# M452x.net
KiCad netlist of a schematic drawn in EAGLE
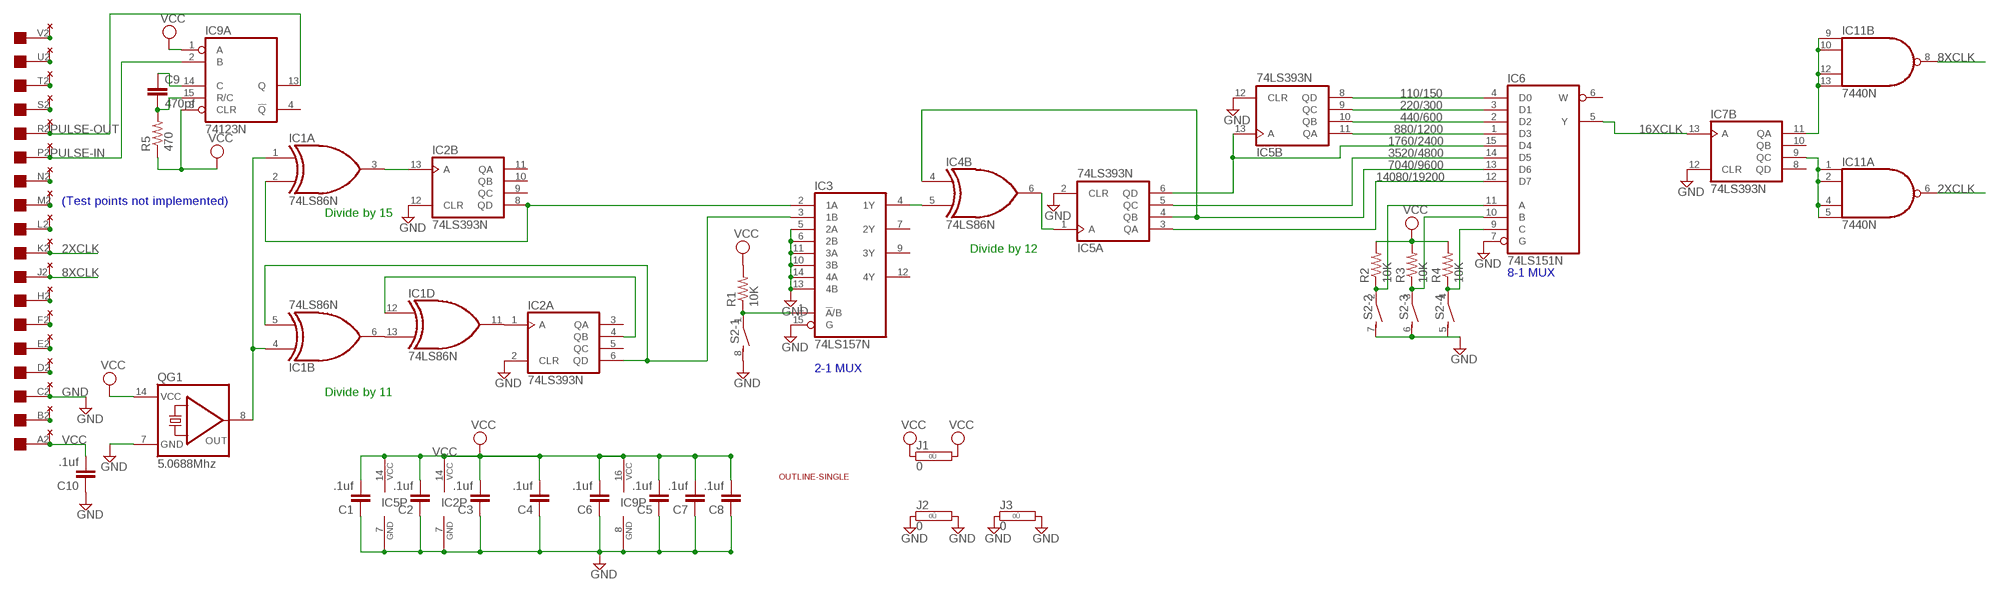
[diagram p0: schematic, sheet 1]

(export (version "E")
  (design (tool "Eeschema 10.0.6"))
  (components
    (comp (ref "C1")
      (value ".1uf")
      (footprint "eagle-import:C050-025X075")
      (libsource (lib "eagle-import") (part "C-EU050-025X075"))
    )
    (comp (ref "C2")
      (value ".1uf")
      (footprint "eagle-import:C050-025X075")
      (libsource (lib "eagle-import") (part "C-EU050-025X075"))
    )
    (comp (ref "C3")
      (value ".1uf")
      (footprint "eagle-import:C050-025X075")
      (libsource (lib "eagle-import") (part "C-EU050-025X075"))
    )
    (comp (ref "C4")
      (value ".1uf")
      (footprint "eagle-import:C050-025X075")
      (libsource (lib "eagle-import") (part "C-EU050-025X075"))
    )
    (comp (ref "C5")
      (value ".1uf")
      (footprint "eagle-import:C050-025X075")
      (libsource (lib "eagle-import") (part "C-EU050-025X075"))
    )
    (comp (ref "C6")
      (value ".1uf")
      (footprint "eagle-import:C050-025X075")
      (libsource (lib "eagle-import") (part "C-EU050-025X075"))
    )
    (comp (ref "C7")
      (value ".1uf")
      (footprint "eagle-import:C050-025X075")
      (libsource (lib "eagle-import") (part "C-EU050-025X075"))
    )
    (comp (ref "C8")
      (value ".1uf")
      (footprint "eagle-import:C050-025X075")
      (libsource (lib "eagle-import") (part "C-EU050-025X075"))
    )
    (comp (ref "C9")
      (value "470pf")
      (footprint "eagle-import:C050-025X075")
      (libsource (lib "eagle-import") (part "C-EU050-025X075"))
    )
    (comp (ref "C10")
      (value ".1uf")
      (footprint "eagle-import:C050-025X075")
      (libsource (lib "eagle-import") (part "C-EU050-025X075"))
    )
    (comp (ref "IC1")
      (value "74LS86N")
      (footprint "eagle-import:DIL14")
      (libsource (lib "eagle-import") (part "7486NLS"))
    )
    (comp (ref "IC2")
      (value "74LS393N")
      (footprint "eagle-import:DIL14")
      (libsource (lib "eagle-import") (part "74393NLS"))
    )
    (comp (ref "IC3")
      (value "74LS157N")
      (footprint "eagle-import:DIL16")
      (libsource (lib "eagle-import") (part "74157NLS"))
    )
    (comp (ref "IC4")
      (value "74LS86N")
      (footprint "eagle-import:DIL14")
      (libsource (lib "eagle-import") (part "7486NLS"))
    )
    (comp (ref "IC5")
      (value "74LS393N")
      (footprint "eagle-import:DIL14")
      (libsource (lib "eagle-import") (part "74393NLS"))
    )
    (comp (ref "IC6")
      (value "74LS151N")
      (footprint "eagle-import:DIL16")
      (libsource (lib "eagle-import") (part "74151N"))
    )
    (comp (ref "IC7")
      (value "74LS393N")
      (footprint "eagle-import:DIL14")
      (libsource (lib "eagle-import") (part "74393NLS"))
    )
    (comp (ref "IC9")
      (value "74123N")
      (footprint "eagle-import:DIL16")
      (libsource (lib "eagle-import") (part "74123N"))
    )
    (comp (ref "IC11")
      (value "7440N")
      (footprint "eagle-import:DIL14")
      (libsource (lib "eagle-import") (part "7420NS"))
    )
    (comp (ref "J1")
      (value "0")
      (footprint "eagle-import:0R_10")
      (libsource (lib "eagle-import") (part "0R"))
    )
    (comp (ref "J2")
      (value "0")
      (footprint "eagle-import:0R_10")
      (libsource (lib "eagle-import") (part "0R"))
    )
    (comp (ref "J3")
      (value "0")
      (footprint "eagle-import:0R_10")
      (libsource (lib "eagle-import") (part "0R"))
    )
    (comp (ref "QG1")
      (value "5.0688Mhz")
      (footprint "eagle-import:DIL14S")
      (libsource (lib "eagle-import") (part "QG5860"))
    )
    (comp (ref "R1")
      (value "10K")
      (footprint "eagle-import:0204_7")
      (libsource (lib "eagle-import") (part "R-US_0204/7"))
    )
    (comp (ref "R2")
      (value "10K")
      (footprint "eagle-import:0204_7")
      (libsource (lib "eagle-import") (part "R-US_0204/7"))
    )
    (comp (ref "R3")
      (value "10K")
      (footprint "eagle-import:0204_7")
      (libsource (lib "eagle-import") (part "R-US_0204/7"))
    )
    (comp (ref "R4")
      (value "10K")
      (footprint "eagle-import:0204_7")
      (libsource (lib "eagle-import") (part "R-US_0204/7"))
    )
    (comp (ref "R5")
      (value "470")
      (footprint "eagle-import:0204_7")
      (libsource (lib "eagle-import") (part "R-US_0204/7"))
    )
    (comp (ref "S2")
      (value "DIP04S")
      (footprint "eagle-import:DIP04S")
      (libsource (lib "eagle-import") (part "DIP04S"))
    )
    (comp (ref "U$2")
      (value "THRU-HOLE1")
      (footprint "eagle-import:THRU-HOLE1")
      (libsource (lib "eagle-import") (part "THRU-HOLE1"))
    )
    (comp (ref "U$3")
      (value "OUTLINE-SINGLE")
      (footprint "eagle-import:SINGLE")
      (libsource (lib "eagle-import") (part "OUTLINE-SINGLE"))
    )
    (comp (ref "U$4")
      (value "EDGE-1")
      (footprint "eagle-import:EDGE-CON1")
      (libsource (lib "eagle-import") (part "EDGE-1"))
    )
  )
  (nets
    (net (code "1") (name "/2XCLK") (class "Default")
      (node (ref "IC11") (pin "6") (pinfunction "O_6") (pintype "output"))
      (node (ref "U$2") (pin "K2") (pinfunction "P$1_K2") (pintype "passive"))
      (node (ref "U$4") (pin "K2") (pinfunction "1_K2") (pintype "bidirectional"))
    )
    (net (code "2") (name "/8XCLK") (class "Default")
      (node (ref "IC11") (pin "8") (pinfunction "O_8") (pintype "output"))
      (node (ref "U$2") (pin "J2") (pinfunction "P$1_J2") (pintype "passive"))
      (node (ref "U$4") (pin "J2") (pinfunction "1_J2") (pintype "bidirectional"))
    )
    (net (code "3") (name "/16XCLK") (class "Default")
      (node (ref "IC6") (pin "5") (pinfunction "Y_5") (pintype "output"))
      (node (ref "IC7") (pin "13") (pinfunction "A_13") (pintype "input"))
    )
    (net (code "4") (name "/110{slash}150") (class "Default")
      (node (ref "IC5") (pin "8") (pinfunction "QD_8") (pintype "output"))
      (node (ref "IC6") (pin "4") (pinfunction "D0_4") (pintype "input"))
    )
    (net (code "5") (name "/220{slash}300") (class "Default")
      (node (ref "IC5") (pin "9") (pinfunction "QC_9") (pintype "output"))
      (node (ref "IC6") (pin "3") (pinfunction "D1_3") (pintype "input"))
    )
    (net (code "6") (name "/440{slash}600") (class "Default")
      (node (ref "IC5") (pin "10") (pinfunction "QB_10") (pintype "output"))
      (node (ref "IC6") (pin "2") (pinfunction "D2_2") (pintype "input"))
    )
    (net (code "7") (name "/880{slash}1200") (class "Default")
      (node (ref "IC5") (pin "11") (pinfunction "QA_11") (pintype "output"))
      (node (ref "IC6") (pin "1") (pinfunction "D3_1") (pintype "input"))
    )
    (net (code "8") (name "/1760{slash}2400") (class "Default")
      (node (ref "IC5") (pin "13") (pinfunction "A_13") (pintype "input"))
      (node (ref "IC5") (pin "6") (pinfunction "QD_6") (pintype "output"))
      (node (ref "IC6") (pin "15") (pinfunction "D4_15") (pintype "input"))
    )
    (net (code "9") (name "/3520{slash}4800") (class "Default")
      (node (ref "IC5") (pin "5") (pinfunction "QC_5") (pintype "output"))
      (node (ref "IC6") (pin "14") (pinfunction "D5_14") (pintype "input"))
    )
    (net (code "10") (name "/7040{slash}9600") (class "Default")
      (node (ref "IC4") (pin "4") (pinfunction "I0_4") (pintype "input"))
      (node (ref "IC5") (pin "4") (pinfunction "QB_4") (pintype "output"))
      (node (ref "IC6") (pin "13") (pinfunction "D6_13") (pintype "input"))
    )
    (net (code "11") (name "/14080{slash}19200") (class "Default")
      (node (ref "IC5") (pin "3") (pinfunction "QA_3") (pintype "output"))
      (node (ref "IC6") (pin "12") (pinfunction "D7_12") (pintype "input"))
    )
    (net (code "12") (name "/PULSE-IN") (class "Default")
      (node (ref "IC9") (pin "2") (pinfunction "B_2") (pintype "input"))
      (node (ref "U$2") (pin "P2") (pinfunction "P$1_P2") (pintype "passive"))
      (node (ref "U$4") (pin "P2") (pinfunction "1_P2") (pintype "bidirectional"))
    )
    (net (code "13") (name "/PULSE-OUT") (class "Default")
      (node (ref "IC9") (pin "13") (pinfunction "Q_13") (pintype "output"))
      (node (ref "U$2") (pin "R2") (pinfunction "P$1_R2") (pintype "passive"))
      (node (ref "U$4") (pin "R2") (pinfunction "1_R2") (pintype "bidirectional"))
    )
    (net (code "14") (name "GND") (class "Default")
      (node (ref "C1") (pin "1") (pinfunction "1_1") (pintype "passive"))
      (node (ref "C10") (pin "1") (pinfunction "1_1") (pintype "passive"))
      (node (ref "C2") (pin "1") (pinfunction "1_1") (pintype "passive"))
      (node (ref "C3") (pin "1") (pinfunction "1_1") (pintype "passive"))
      (node (ref "C4") (pin "1") (pinfunction "1_1") (pintype "passive"))
      (node (ref "C5") (pin "1") (pinfunction "1_1") (pintype "passive"))
      (node (ref "C6") (pin "1") (pinfunction "1_1") (pintype "passive"))
      (node (ref "C7") (pin "1") (pinfunction "1_1") (pintype "passive"))
      (node (ref "C8") (pin "1") (pinfunction "1_1") (pintype "passive"))
      (node (ref "IC2") (pin "12") (pinfunction "CLR_12") (pintype "input"))
      (node (ref "IC2") (pin "2") (pinfunction "CLR_2") (pintype "input"))
      (node (ref "IC2") (pin "7") (pinfunction "GND_7") (pintype "power_in"))
      (node (ref "IC3") (pin "10") (pinfunction "3B_10") (pintype "input"))
      (node (ref "IC3") (pin "11") (pinfunction "3A_11") (pintype "input"))
      (node (ref "IC3") (pin "13") (pinfunction "4B_13") (pintype "input"))
      (node (ref "IC3") (pin "14") (pinfunction "4A_14") (pintype "input"))
      (node (ref "IC3") (pin "15") (pinfunction "G_15") (pintype "input"))
      (node (ref "IC3") (pin "5") (pinfunction "2A_5") (pintype "input"))
      (node (ref "IC3") (pin "6") (pinfunction "2B_6") (pintype "input"))
      (node (ref "IC5") (pin "12") (pinfunction "CLR_12") (pintype "input"))
      (node (ref "IC5") (pin "2") (pinfunction "CLR_2") (pintype "input"))
      (node (ref "IC5") (pin "7") (pinfunction "GND_7") (pintype "power_in"))
      (node (ref "IC6") (pin "7") (pinfunction "G_7") (pintype "input"))
      (node (ref "IC7") (pin "12") (pinfunction "CLR_12") (pintype "input"))
      (node (ref "IC9") (pin "8") (pinfunction "GND_8") (pintype "power_in"))
      (node (ref "J2") (pin "1") (pinfunction "1_1") (pintype "passive"))
      (node (ref "J2") (pin "2") (pinfunction "2_2") (pintype "passive"))
      (node (ref "J3") (pin "1") (pinfunction "1_1") (pintype "passive"))
      (node (ref "J3") (pin "2") (pinfunction "2_2") (pintype "passive"))
      (node (ref "QG1") (pin "7") (pinfunction "GND_7") (pintype "power_in"))
      (node (ref "S2") (pin "5") (pinfunction "2_5") (pintype "passive"))
      (node (ref "S2") (pin "6") (pinfunction "2_6") (pintype "passive"))
      (node (ref "S2") (pin "7") (pinfunction "2_7") (pintype "passive"))
      (node (ref "S2") (pin "8") (pinfunction "2_8") (pintype "passive"))
      (node (ref "U$2") (pin "C2") (pinfunction "P$1_C2") (pintype "passive"))
      (node (ref "U$4") (pin "C2") (pinfunction "1_C2") (pintype "bidirectional"))
    )
    (net (code "15") (name "Net-(IC1A-I0)") (class "Default")
      (node (ref "IC1") (pin "1") (pinfunction "I0_1") (pintype "input"))
      (node (ref "IC1") (pin "4") (pinfunction "I0_4") (pintype "input"))
      (node (ref "QG1") (pin "8") (pinfunction "OUT_8") (pintype "output"))
    )
    (net (code "16") (name "Net-(IC1A-I1)") (class "Default")
      (node (ref "IC1") (pin "2") (pinfunction "I1_2") (pintype "input"))
      (node (ref "IC2") (pin "8") (pinfunction "QD_8") (pintype "output"))
      (node (ref "IC3") (pin "2") (pinfunction "1A_2") (pintype "input"))
    )
    (net (code "17") (name "Net-(IC1A-O)") (class "Default")
      (node (ref "IC1") (pin "3") (pinfunction "O_3") (pintype "output"))
      (node (ref "IC2") (pin "13") (pinfunction "A_13") (pintype "input"))
    )
    (net (code "18") (name "Net-(IC1B-I1)") (class "Default")
      (node (ref "IC1") (pin "5") (pinfunction "I1_5") (pintype "input"))
      (node (ref "IC2") (pin "6") (pinfunction "QD_6") (pintype "output"))
      (node (ref "IC3") (pin "3") (pinfunction "1B_3") (pintype "input"))
    )
    (net (code "19") (name "Net-(IC1B-O)") (class "Default")
      (node (ref "IC1") (pin "13") (pinfunction "I1_13") (pintype "input"))
      (node (ref "IC1") (pin "6") (pinfunction "O_6") (pintype "output"))
    )
    (net (code "20") (name "Net-(IC1D-I0)") (class "Default")
      (node (ref "IC1") (pin "12") (pinfunction "I0_12") (pintype "input"))
      (node (ref "IC2") (pin "4") (pinfunction "QB_4") (pintype "output"))
    )
    (net (code "21") (name "Net-(IC1D-O)") (class "Default")
      (node (ref "IC1") (pin "11") (pinfunction "O_11") (pintype "output"))
      (node (ref "IC2") (pin "1") (pinfunction "A_1") (pintype "input"))
    )
    (net (code "22") (name "Net-(IC3A-1Y)") (class "Default")
      (node (ref "IC3") (pin "4") (pinfunction "1Y_4") (pintype "output"))
      (node (ref "IC4") (pin "5") (pinfunction "I1_5") (pintype "input"))
    )
    (net (code "23") (name "Net-(IC3A-~{A}{slash}B)") (class "Default")
      (node (ref "IC3") (pin "1") (pinfunction "~{A}/B_1") (pintype "input"))
      (node (ref "R1") (pin "1") (pinfunction "1_1") (pintype "passive"))
      (node (ref "S2") (pin "1") (pinfunction "1_1") (pintype "passive"))
    )
    (net (code "24") (name "Net-(IC4B-O)") (class "Default")
      (node (ref "IC4") (pin "6") (pinfunction "O_6") (pintype "output"))
      (node (ref "IC5") (pin "1") (pinfunction "A_1") (pintype "input"))
    )
    (net (code "25") (name "Net-(IC6A-A)") (class "Default")
      (node (ref "IC6") (pin "11") (pinfunction "A_11") (pintype "input"))
      (node (ref "R2") (pin "1") (pinfunction "1_1") (pintype "passive"))
      (node (ref "S2") (pin "2") (pinfunction "1_2") (pintype "passive"))
    )
    (net (code "26") (name "Net-(IC6A-B)") (class "Default")
      (node (ref "IC6") (pin "10") (pinfunction "B_10") (pintype "input"))
      (node (ref "R3") (pin "1") (pinfunction "1_1") (pintype "passive"))
      (node (ref "S2") (pin "3") (pinfunction "1_3") (pintype "passive"))
    )
    (net (code "27") (name "Net-(IC6A-C)") (class "Default")
      (node (ref "IC6") (pin "9") (pinfunction "C_9") (pintype "input"))
      (node (ref "R4") (pin "1") (pinfunction "1_1") (pintype "passive"))
      (node (ref "S2") (pin "4") (pinfunction "1_4") (pintype "passive"))
    )
    (net (code "28") (name "Net-(IC9A-C)") (class "Default")
      (node (ref "C9") (pin "1") (pinfunction "1_1") (pintype "passive"))
      (node (ref "IC9") (pin "14") (pinfunction "C_14") (pintype "input"))
    )
    (net (code "29") (name "Net-(IC9A-R{slash}C)") (class "Default")
      (node (ref "C9") (pin "2") (pinfunction "2_2") (pintype "passive"))
      (node (ref "IC9") (pin "15") (pinfunction "R/C_15") (pintype "input"))
      (node (ref "R5") (pin "2") (pinfunction "2_2") (pintype "passive"))
    )
    (net (code "30") (name "Net-(IC11A-I0)") (class "Default")
      (node (ref "IC11") (pin "1") (pinfunction "I0_1") (pintype "input"))
      (node (ref "IC11") (pin "2") (pinfunction "I1_2") (pintype "input"))
      (node (ref "IC11") (pin "4") (pinfunction "I2_4") (pintype "input"))
      (node (ref "IC11") (pin "5") (pinfunction "I3_5") (pintype "input"))
      (node (ref "IC7") (pin "9") (pinfunction "QC_9") (pintype "output"))
    )
    (net (code "31") (name "Net-(IC11B-I0)") (class "Default")
      (node (ref "IC11") (pin "10") (pinfunction "I1_10") (pintype "input"))
      (node (ref "IC11") (pin "12") (pinfunction "I2_12") (pintype "input"))
      (node (ref "IC11") (pin "13") (pinfunction "I3_13") (pintype "input"))
      (node (ref "IC11") (pin "9") (pinfunction "I0_9") (pintype "input"))
      (node (ref "IC7") (pin "11") (pinfunction "QA_11") (pintype "output"))
    )
    (net (code "32") (name "Net-(U$2B-P$1)") (class "Default")
      (node (ref "U$2") (pin "B2") (pinfunction "P$1_B2") (pintype "passive"))
      (node (ref "U$4") (pin "B2") (pinfunction "1_B2") (pintype "bidirectional"))
    )
    (net (code "33") (name "Net-(U$2D-P$1)") (class "Default")
      (node (ref "U$2") (pin "D2") (pinfunction "P$1_D2") (pintype "passive"))
      (node (ref "U$4") (pin "D2") (pinfunction "1_D2") (pintype "bidirectional"))
    )
    (net (code "34") (name "Net-(U$2E-P$1)") (class "Default")
      (node (ref "U$2") (pin "E2") (pinfunction "P$1_E2") (pintype "passive"))
      (node (ref "U$4") (pin "E2") (pinfunction "1_E2") (pintype "bidirectional"))
    )
    (net (code "35") (name "Net-(U$2F-P$1)") (class "Default")
      (node (ref "U$2") (pin "F2") (pinfunction "P$1_F2") (pintype "passive"))
      (node (ref "U$4") (pin "F2") (pinfunction "1_F2") (pintype "bidirectional"))
    )
    (net (code "36") (name "Net-(U$2G-P$1)") (class "Default")
      (node (ref "U$2") (pin "H2") (pinfunction "P$1_H2") (pintype "passive"))
      (node (ref "U$4") (pin "H2") (pinfunction "1_H2") (pintype "bidirectional"))
    )
    (net (code "37") (name "Net-(U$2J-P$1)") (class "Default")
      (node (ref "U$2") (pin "L2") (pinfunction "P$1_L2") (pintype "passive"))
      (node (ref "U$4") (pin "L2") (pinfunction "1_L2") (pintype "bidirectional"))
    )
    (net (code "38") (name "Net-(U$2K-P$1)") (class "Default")
      (node (ref "U$2") (pin "M2") (pinfunction "P$1_M2") (pintype "passive"))
      (node (ref "U$4") (pin "M2") (pinfunction "1_M2") (pintype "bidirectional"))
    )
    (net (code "39") (name "Net-(U$2L-P$1)") (class "Default")
      (node (ref "U$2") (pin "N2") (pinfunction "P$1_N2") (pintype "passive"))
      (node (ref "U$4") (pin "N2") (pinfunction "1_N2") (pintype "bidirectional"))
    )
    (net (code "40") (name "Net-(U$2O-P$1)") (class "Default")
      (node (ref "U$2") (pin "S2") (pinfunction "P$1_S2") (pintype "passive"))
      (node (ref "U$4") (pin "S2") (pinfunction "1_S2") (pintype "bidirectional"))
    )
    (net (code "41") (name "Net-(U$2P-P$1)") (class "Default")
      (node (ref "U$2") (pin "T2") (pinfunction "P$1_T2") (pintype "passive"))
      (node (ref "U$4") (pin "T2") (pinfunction "1_T2") (pintype "bidirectional"))
    )
    (net (code "42") (name "Net-(U$2Q-P$1)") (class "Default")
      (node (ref "U$2") (pin "U2") (pinfunction "P$1_U2") (pintype "passive"))
      (node (ref "U$4") (pin "U2") (pinfunction "1_U2") (pintype "bidirectional"))
    )
    (net (code "43") (name "Net-(U$2R-P$1)") (class "Default")
      (node (ref "U$2") (pin "V2") (pinfunction "P$1_V2") (pintype "passive"))
      (node (ref "U$4") (pin "V2") (pinfunction "1_V2") (pintype "bidirectional"))
    )
    (net (code "44") (name "VCC") (class "Default")
      (node (ref "C1") (pin "2") (pinfunction "2_2") (pintype "passive"))
      (node (ref "C10") (pin "2") (pinfunction "2_2") (pintype "passive"))
      (node (ref "C2") (pin "2") (pinfunction "2_2") (pintype "passive"))
      (node (ref "C3") (pin "2") (pinfunction "2_2") (pintype "passive"))
      (node (ref "C4") (pin "2") (pinfunction "2_2") (pintype "passive"))
      (node (ref "C5") (pin "2") (pinfunction "2_2") (pintype "passive"))
      (node (ref "C6") (pin "2") (pinfunction "2_2") (pintype "passive"))
      (node (ref "C7") (pin "2") (pinfunction "2_2") (pintype "passive"))
      (node (ref "C8") (pin "2") (pinfunction "2_2") (pintype "passive"))
      (node (ref "IC2") (pin "14") (pinfunction "VCC_14") (pintype "power_in"))
      (node (ref "IC5") (pin "14") (pinfunction "VCC_14") (pintype "power_in"))
      (node (ref "IC9") (pin "1") (pinfunction "A_1") (pintype "input"))
      (node (ref "IC9") (pin "16") (pinfunction "VCC_16") (pintype "power_in"))
      (node (ref "IC9") (pin "3") (pinfunction "CLR_3") (pintype "input"))
      (node (ref "J1") (pin "1") (pinfunction "1_1") (pintype "passive"))
      (node (ref "J1") (pin "2") (pinfunction "2_2") (pintype "passive"))
      (node (ref "QG1") (pin "14") (pinfunction "VCC_14") (pintype "power_in"))
      (node (ref "R1") (pin "2") (pinfunction "2_2") (pintype "passive"))
      (node (ref "R2") (pin "2") (pinfunction "2_2") (pintype "passive"))
      (node (ref "R3") (pin "2") (pinfunction "2_2") (pintype "passive"))
      (node (ref "R4") (pin "2") (pinfunction "2_2") (pintype "passive"))
      (node (ref "R5") (pin "1") (pinfunction "1_1") (pintype "passive"))
      (node (ref "U$2") (pin "A2") (pinfunction "P$1_A2") (pintype "passive"))
      (node (ref "U$4") (pin "A2") (pinfunction "1_A2") (pintype "bidirectional"))
    )
    (net (code "45") (name "unconnected-(IC2A-QA-Pad3)") (class "Default")
      (node (ref "IC2") (pin "3") (pinfunction "QA_3") (pintype "output"))
    )
    (net (code "46") (name "unconnected-(IC2A-QC-Pad5)") (class "Default")
      (node (ref "IC2") (pin "5") (pinfunction "QC_5") (pintype "output"))
    )
    (net (code "47") (name "unconnected-(IC2B-QA-Pad11)") (class "Default")
      (node (ref "IC2") (pin "11") (pinfunction "QA_11") (pintype "output"))
    )
    (net (code "48") (name "unconnected-(IC2B-QB-Pad10)") (class "Default")
      (node (ref "IC2") (pin "10") (pinfunction "QB_10") (pintype "output"))
    )
    (net (code "49") (name "unconnected-(IC2B-QC-Pad9)") (class "Default")
      (node (ref "IC2") (pin "9") (pinfunction "QC_9") (pintype "output"))
    )
    (net (code "50") (name "unconnected-(IC3A-2Y-Pad7)") (class "Default")
      (node (ref "IC3") (pin "7") (pinfunction "2Y_7") (pintype "output"))
    )
    (net (code "51") (name "unconnected-(IC3A-3Y-Pad9)") (class "Default")
      (node (ref "IC3") (pin "9") (pinfunction "3Y_9") (pintype "output"))
    )
    (net (code "52") (name "unconnected-(IC3A-4Y-Pad12)") (class "Default")
      (node (ref "IC3") (pin "12") (pinfunction "4Y_12") (pintype "output"))
    )
    (net (code "53") (name "unconnected-(IC6A-W-Pad6)") (class "Default")
      (node (ref "IC6") (pin "6") (pinfunction "W_6") (pintype "output"))
    )
    (net (code "54") (name "unconnected-(IC7B-QB-Pad10)") (class "Default")
      (node (ref "IC7") (pin "10") (pinfunction "QB_10") (pintype "output"))
    )
    (net (code "55") (name "unconnected-(IC7B-QD-Pad8)") (class "Default")
      (node (ref "IC7") (pin "8") (pinfunction "QD_8") (pintype "output"))
    )
    (net (code "56") (name "unconnected-(IC9A-~{Q}-Pad4)") (class "Default")
      (node (ref "IC9") (pin "4") (pinfunction "~{Q}_4") (pintype "output"))
    )
  )
)
